# Externo.net
KiCad netlist of a schematic drawn in Altium Designer
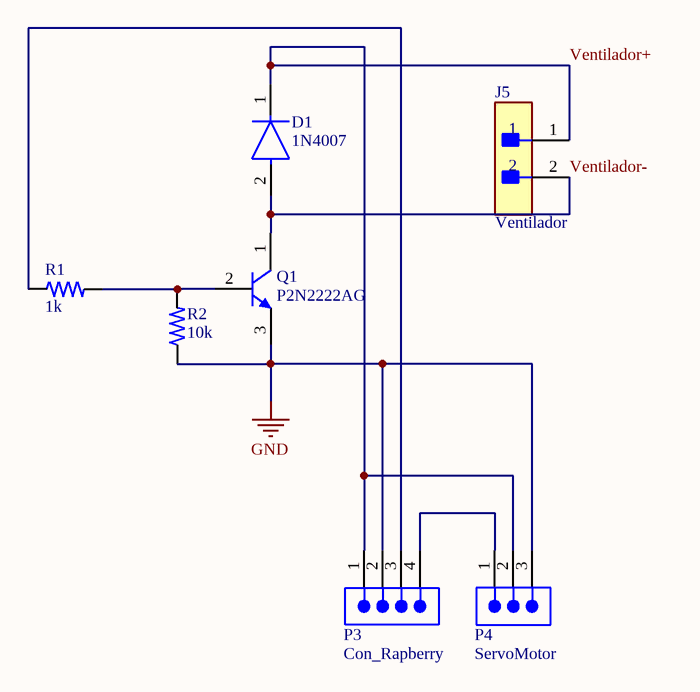
[diagram p0: Externo.SchDoc]

(export (version "E")
  (design (tool "Eeschema 10.0.6"))
  (components
    (comp (ref "D1")
      (value "1N4007")
      (footprint "FP-1N4007-MFG")
      (description "Rectifier diode 1000 V 1 A DO-41, ,")
      (fields
        (field (name "MANUFACTURER") "Diotec")
        (field (name "OCTOPART") "https://octopart.com/1n4007-diotec-4040411")
      )
      (libsource (lib "Altium Content Vault") (part "d7152d700b627762746794eb795d46e"))
    )
    (comp (ref "J5")
      (value "Ventilador")
      (footprint "FP-B2B-XH-A_LF_SN-MFG")
      (description "CONN HEADER VERT 2POS 2.5MM")
      (libsource (lib "Altium Content Vault") (part "3bc925449376181038e59eaffc5286c"))
    )
    (comp (ref "P3")
      (value "Con_Rapberry")
      (footprint "SMTC-TSW-104-08-X-S")
      (description "0.025\" SQ Post Header, Through-hole, Vertical, -55 to 125 degC, 2.54 mm Pitch, 4-Pin, Male, RoHS")
      (fields (field (name "MANUFACTURER") "Samtec") (field (name "PARTNUMBER") "TSW-104-08-G-S"))
      (libsource (lib "Altium Content Vault") (part "SMTC-TSW-104-08-X-S"))
    )
    (comp (ref "P4")
      (value "ServoMotor")
      (footprint "SMTC-TSW-103-07-X-S")
      (description "0.025\" SQ Post Header, Through-hole, Vertical, -55 to 105 degC, 2.54 mm Pitch, 3-Pin, Male, RoHS")
      (fields (field (name "PARTNUMBER") "TSW-103-07-T-S") (field (name "MANUFACTURER") "Samtec"))
      (libsource (lib "Altium Content Vault") (part "SMTC-TSW-103-X-X-S-X"))
    )
    (comp (ref "Q1")
      (value "P2N2222AG")
      (footprint "ONSC-TO-92-3-29-11")
      (description "Amplifier Transistor, NPN Silicon, 3-Pin TO-92, Pb-Free, Bulk Box")
      (fields (field (name "MANUFACTURER") "On Semiconductor"))
      (libsource (lib "Altium Content Vault") (part "ONSC-NPN-C1B2E3-3"))
    )
    (comp (ref "R1")
      (value "1k")
      (footprint "RESAD640W45L370D200")
      (description "2.4 kOhms Â±1% 0.25W, 1/4W Through Hole Resistor Axial - Metal Film")
      (fields (field (name "MF") "TE Connectivity Passive Product") (field (name "MP") "LR0204F2K4"))
      (libsource (lib "LR0204F2K4") (part "LR0204F2K4"))
    )
    (comp (ref "R2")
      (value "10k")
      (footprint "RESAD640W45L370D200")
      (description "2.4 kOhms Â±1% 0.25W, 1/4W Through Hole Resistor Axial - Metal Film")
      (fields (field (name "MF") "TE Connectivity Passive Product") (field (name "MP") "LR0204F2K4"))
      (libsource (lib "LR0204F2K4") (part "LR0204F2K4"))
    )
  )
  (nets
    (net (code "1") (name "/Ventilador+") (class "Default")
      (node (ref "D1") (pin "1") (pinfunction "C_1") (pintype "passive"))
      (node (ref "J5") (pin "1") (pinfunction "1_1") (pintype "passive"))
      (node (ref "P3") (pin "1") (pinfunction "1_1") (pintype "passive"))
      (node (ref "P4") (pin "2") (pinfunction "2_2") (pintype "passive"))
    )
    (net (code "2") (name "/Ventilador-") (class "Default")
      (node (ref "D1") (pin "2") (pinfunction "A_2") (pintype "passive"))
      (node (ref "J5") (pin "2") (pinfunction "2_2") (pintype "passive"))
      (node (ref "Q1") (pin "1") (pinfunction "C_1") (pintype "passive"))
    )
    (net (code "3") (name "GND") (class "Default")
      (node (ref "P3") (pin "2") (pinfunction "2_2") (pintype "passive"))
      (node (ref "P4") (pin "3") (pinfunction "3_3") (pintype "passive"))
      (node (ref "Q1") (pin "3") (pinfunction "E_3") (pintype "passive"))
      (node (ref "R2") (pin "1") (pinfunction "1_1") (pintype "passive"))
    )
    (net (code "4") (name "Net-(P3-Pad3)") (class "Default")
      (node (ref "P3") (pin "3") (pinfunction "3_3") (pintype "passive"))
      (node (ref "R1") (pin "1") (pinfunction "1_1") (pintype "passive"))
    )
    (net (code "5") (name "Net-(P3-Pad4)") (class "Default")
      (node (ref "P3") (pin "4") (pinfunction "4_4") (pintype "passive"))
      (node (ref "P4") (pin "1") (pinfunction "1_1") (pintype "passive"))
    )
    (net (code "6") (name "Net-(Q1-B)") (class "Default")
      (node (ref "Q1") (pin "2") (pinfunction "B_2") (pintype "passive"))
      (node (ref "R1") (pin "2") (pinfunction "2_2") (pintype "passive"))
      (node (ref "R2") (pin "2") (pinfunction "2_2") (pintype "passive"))
    )
  )
)
